# MGD_SCH1.net
KiCad netlist of a schematic drawn in Altium Designer
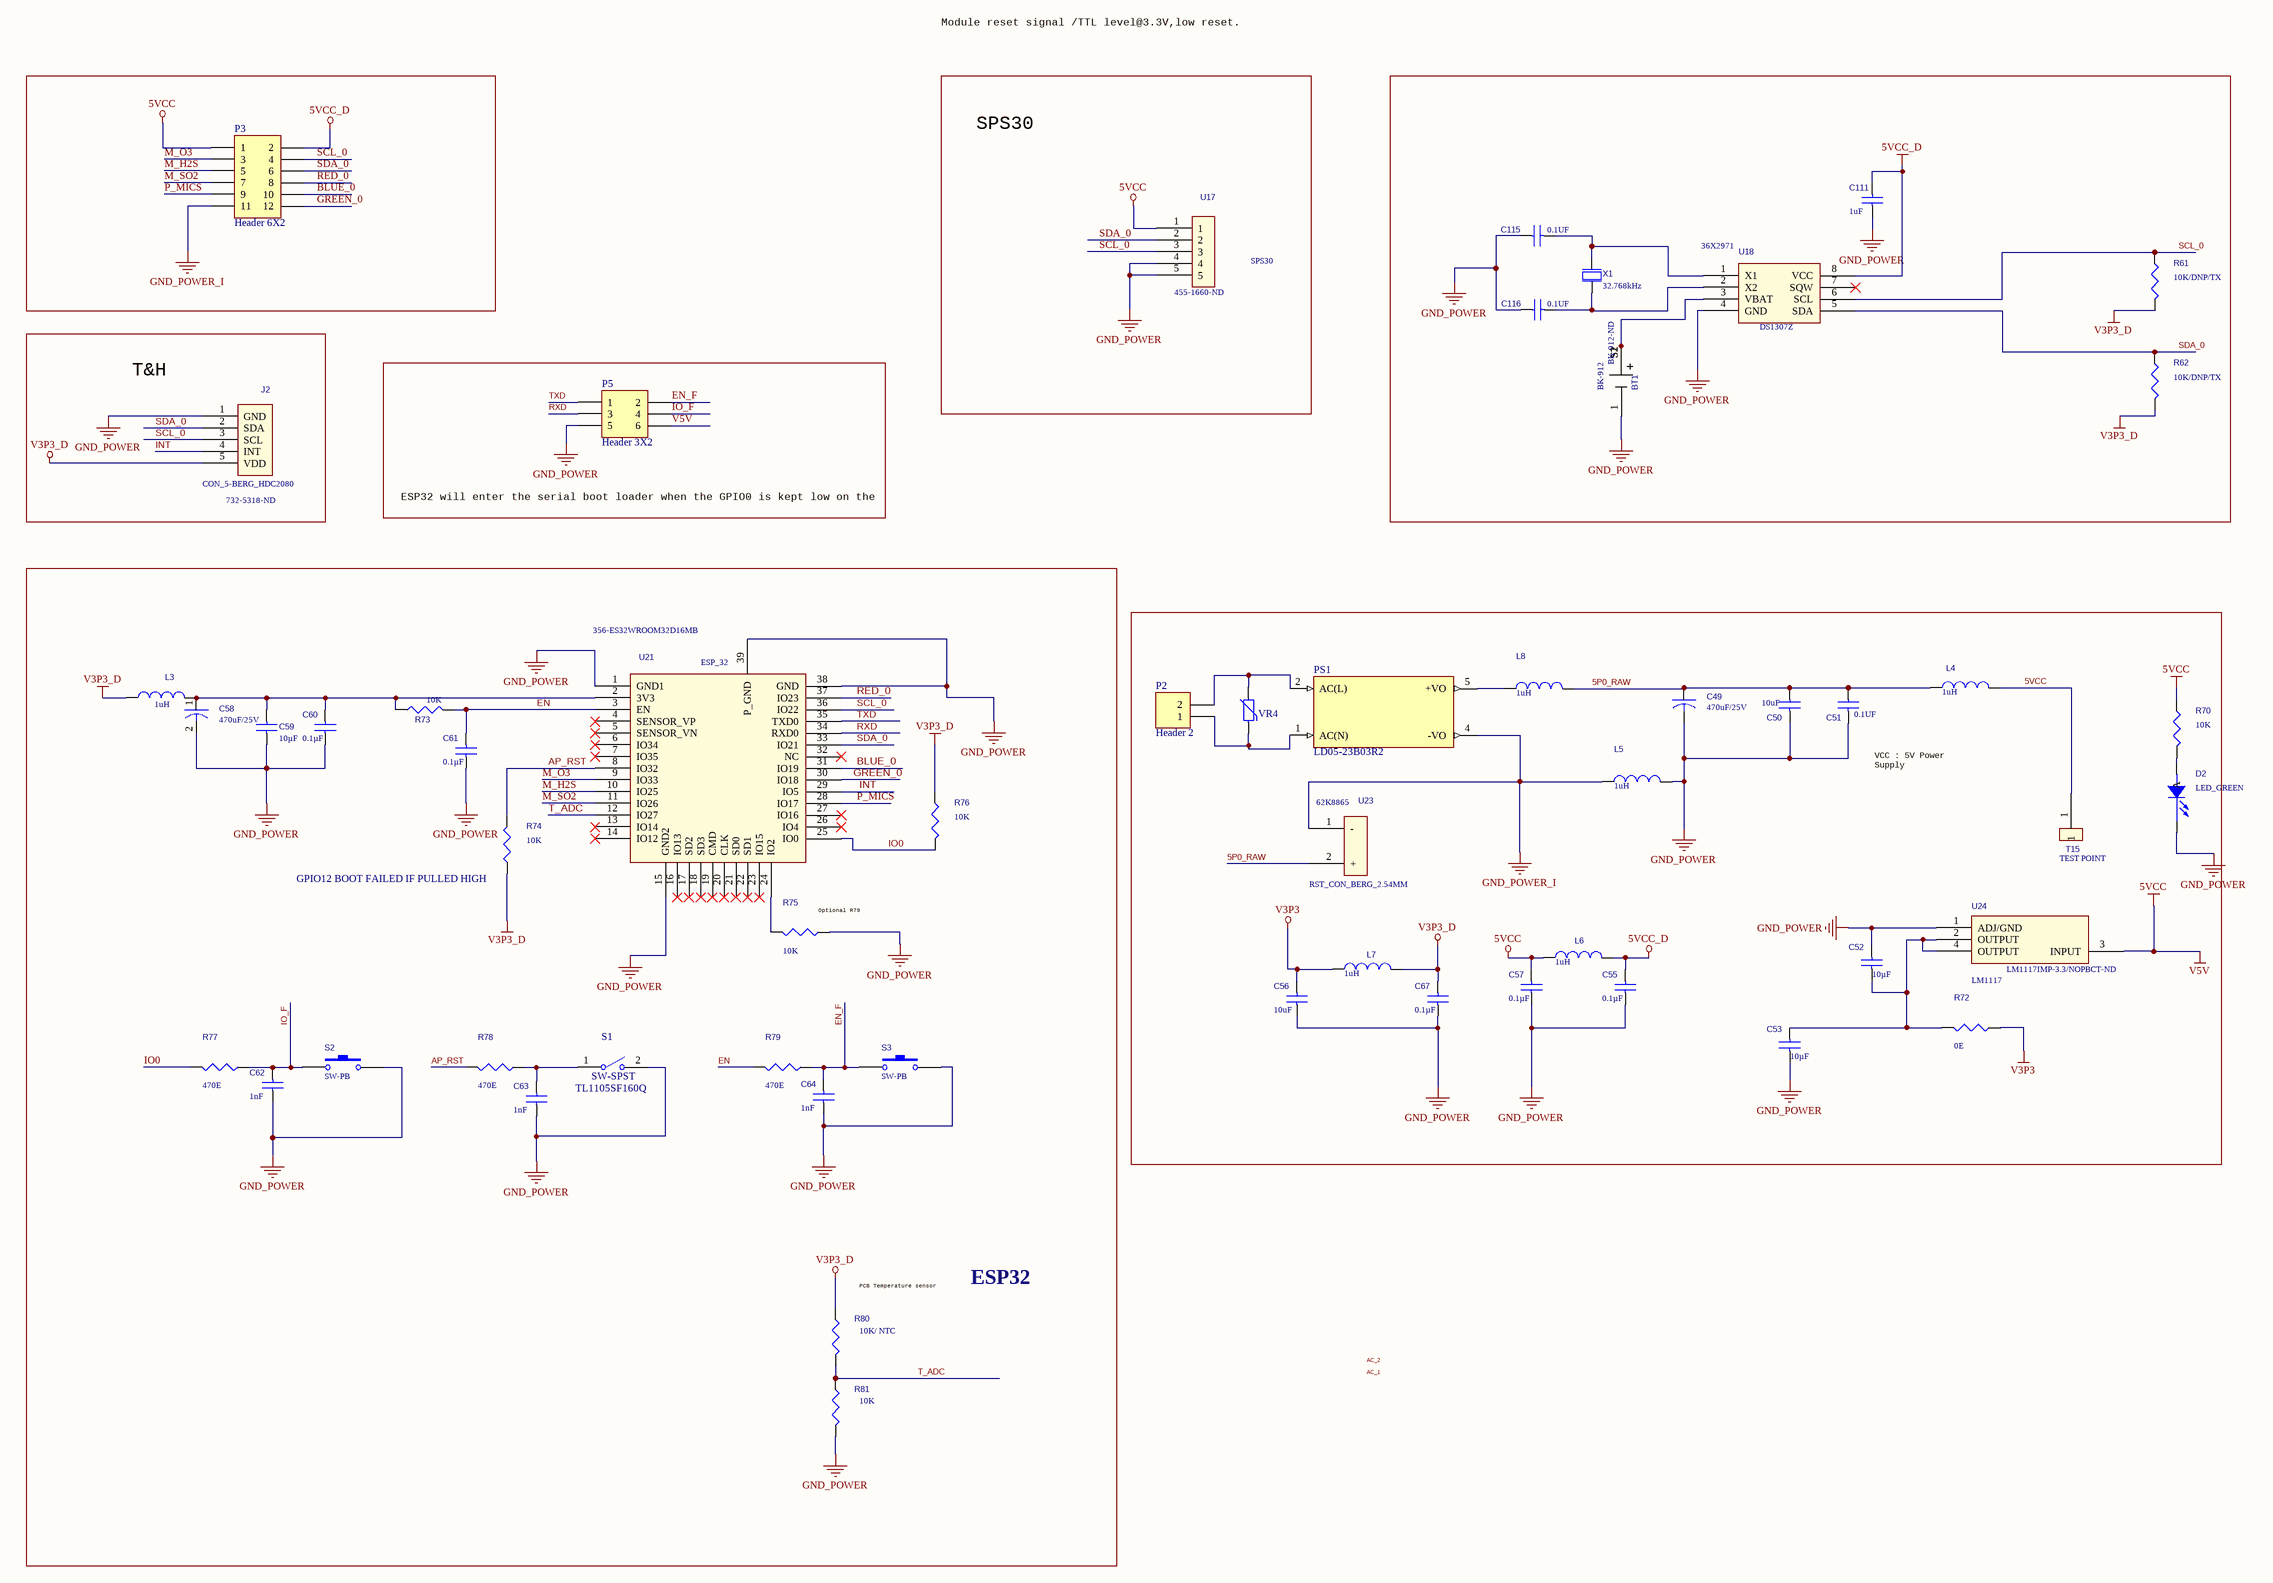
[diagram p0: MGD.SCH1.SchDoc]

(export (version "E")
  (design (tool "Eeschema 10.0.6"))
  (components
    (comp (ref "BT1")
      (value "BK-912")
      (footprint "BT1")
      (description "BATTERY RETAINER COIN 20MM SMD")
      (fields (field (name "MF") "MPD") (field (name "SUPPLIER PART NUMBER 1") "BK-912-ND"))
      (libsource (lib "BK-912") (part "BK-912"))
    )
    (comp (ref "C49")
      (value "470uF/25V")
      (footprint "C16, C49, C58")
      (description "CAP ALUM 470UF 20% 50V RADIAL")
      (fields (field (name "PART NUMBER") "871-B41896E6477M000"))
      (libsource (lib "") (part "CAP_1"))
    )
    (comp (ref "C50")
      (value "10uF")
      (footprint "C0603")
      (description "CAP CER 22UF 10V X5R 0603")
      (fields (field (name "PART NUMBER") "GRM188R61A226ME15D"))
      (libsource (lib "*") (part "CAP NP"))
    )
    (comp (ref "C51")
      (value "0.1UF")
      (footprint "C0603")
      (description "CAP CER 22UF 10V X5R 0603")
      (fields (field (name "PART NUMBER") "GRM188R61A226ME15D"))
      (libsource (lib "*") (part "CAP NP"))
    )
    (comp (ref "C52")
      (value "10µF")
      (footprint "C0603")
      (description "CAP CER SMD 10µF/35V")
      (fields
        (field (name "MANUFACTURER") "Taiyo Yuden")
        (field (name "MANUFACTURER PART NUMBER") "GMK316AB7106KL-TR")
      )
      (libsource (lib "Passive Component") (part "CAP_C_10µF/35V"))
    )
    (comp (ref "C53")
      (value "10µF")
      (footprint "C0603")
      (description "CAP CER SMD 10µF/35V")
      (fields
        (field (name "MANUFACTURER") "Taiyo Yuden")
        (field (name "MANUFACTURER PART NUMBER") "GMK316AB7106KL-TR")
      )
      (libsource (lib "Passive Component") (part "CAP_C_10µF/35V"))
    )
    (comp (ref "C55")
      (value "0.1µF")
      (footprint "C0603")
      (description "CAP CER SMD 0.1µF/16V")
      (fields
        (field (name "MANUFACTURER") "Murata Electronics North America")
        (field (name "MANUFACTURER PART NUMBER") "GRM155R61H104KE19D")
      )
      (libsource (lib "Passive Component") (part "CAP_C_0.1µF/16V"))
    )
    (comp (ref "C56")
      (value "10uF")
      (footprint "C0603")
      (description "CAP CER SMD 0.1µF/16V")
      (fields
        (field (name "MANUFACTURER") "Murata Electronics North America")
        (field (name "MANUFACTURER PART NUMBER") "GRM155R61H104KE19D")
      )
      (libsource (lib "Passive Component") (part "CAP_C_0.1µF/16V"))
    )
    (comp (ref "C57")
      (value "0.1µF")
      (footprint "C0603")
      (description "CAP CER SMD 0.1µF/16V")
      (fields
        (field (name "MANUFACTURER") "Murata Electronics North America")
        (field (name "MANUFACTURER PART NUMBER") "GRM155R61H104KE19D")
      )
      (libsource (lib "Passive Component") (part "CAP_C_0.1µF/16V"))
    )
    (comp (ref "C58")
      (value "470uF/25V")
      (footprint "C16, C49, C58")
      (description "CAP ALUM 470UF 20% 50V RADIAL")
      (fields (field (name "PART NUMBER") "871-B41896E6477M000"))
      (libsource (lib "*") (part "CAP"))
    )
    (comp (ref "C59")
      (value "10µF")
      (footprint "C0603")
      (description "CAP CER SMD 10µF/10V")
      (fields
        (field (name "MANUFACTURER") "Yageo")
        (field (name "MANUFACTURER PART NUMBER") "CC0805ZKY5V6BB106")
      )
      (libsource (lib "Passive Component") (part "CAP_C_10µF/10V"))
    )
    (comp (ref "C60")
      (value "0.1µF")
      (footprint "C0603")
      (description "CAP CER SMD 0.1µF/16V")
      (fields
        (field (name "MANUFACTURER") "Murata Electronics North America")
        (field (name "MANUFACTURER PART NUMBER") "CC0603KRX7R7BB104")
      )
      (libsource (lib "Passive Component") (part "CAP_C_0.1µF/16V"))
    )
    (comp (ref "C61")
      (value "0.1µF")
      (footprint "C0603")
      (description "CAP CER SMD 0.1µF/16V")
      (fields
        (field (name "MANUFACTURER") "Murata Electronics North America")
        (field (name "MANUFACTURER PART NUMBER") "GRM155R61H104KE19D")
      )
      (libsource (lib "Passive Component") (part "CAP_C_0.1µF/16V"))
    )
    (comp (ref "C62")
      (value "1nF")
      (footprint "C0603")
      (description "CAP CER SMD 0.1µF/16V")
      (fields
        (field (name "MANUFACTURER") "Murata Electronics North America")
        (field (name "MANUFACTURER PART NUMBER") "GRM155R61H104KE19D")
      )
      (libsource (lib "Passive Component") (part "CAP_C_0.1µF/16V"))
    )
    (comp (ref "C63")
      (value "1nF")
      (footprint "C0603")
      (description "CAP CER SMD 0.1µF/16V")
      (fields
        (field (name "MANUFACTURER") "Murata Electronics North America")
        (field (name "MANUFACTURER PART NUMBER") "GRM155R61H104KE19D")
      )
      (libsource (lib "Passive Component") (part "CAP_C_0.1µF/16V"))
    )
    (comp (ref "C64")
      (value "1nF")
      (footprint "C0603")
      (description "CAP CER SMD 0.1µF/16V")
      (fields
        (field (name "MANUFACTURER") "Murata Electronics North America")
        (field (name "MANUFACTURER PART NUMBER") "GRM155R61H104KE19D")
      )
      (libsource (lib "Passive Component") (part "CAP_C_0.1µF/16V"))
    )
    (comp (ref "C67")
      (value "0.1µF")
      (footprint "C0603")
      (description "CAP CER SMD 0.1µF/16V")
      (fields
        (field (name "MANUFACTURER") "Murata Electronics North America")
        (field (name "MANUFACTURER PART NUMBER") "GRM155R61H104KE19D")
      )
      (libsource (lib "Passive Component") (part "CAP_C_0.1µF/16V"))
    )
    (comp (ref "C111")
      (value "1uF")
      (footprint "C0603")
      (description "CAP CER SMD 0.1µF/16V")
      (fields
        (field (name "MANUFACTURER") "Murata Electronics North America")
        (field (name "MANUFACTURER PART NUMBER") "GRM155R61H104KE19D")
      )
      (libsource (lib "Passive Component") (part "CAP_C_0.1µF/16V"))
    )
    (comp (ref "C115")
      (value "0.1UF")
      (footprint "C0603")
      (description "CAP CER 22UF 10V X5R 0603")
      (fields (field (name "PART NUMBER") "GRM188R61A226ME15D"))
      (libsource (lib "*") (part "CAP NP"))
    )
    (comp (ref "C116")
      (value "0.1UF")
      (footprint "C0603")
      (description "CAP CER 22UF 10V X5R 0603")
      (fields (field (name "PART NUMBER") "GRM188R61A226ME15D"))
      (libsource (lib "*") (part "CAP NP"))
    )
    (comp (ref "D2")
      (value "LED_GREEN")
      (footprint "D2              L0603")
      (description "LED GREEN CLEAR THIN 0603 SMD")
      (fields
        (field (name "DISTRIBUTOR PART NUMBER") "160-1443-1-ND")
        (field (name "MANUFACTURER PART NUMBER") "160-1443-2-ND")
      )
      (libsource (lib "*") (part "LED"))
    )
    (comp (ref "J2")
      (value "CON_5-BERG_HDC2080")
      (footprint "J2")
      (description "CONN HEADER VERT 5POS 2.54MM")
      (fields
        (field (name "PART NUMBER") "61300511121")
        (field (name "SUPPLIER PART NUMBER 1") "732-5318-ND")
      )
      (libsource (lib "*") (part "5_PIN_CON_0"))
    )
    (comp (ref "L3")
      (value "1uH")
      (footprint "L3, L4, L5, L6, L7")
      (description "FERRITE BEAD 120 OHM 0603 1LN")
      (fields (field (name "PART NUMBER") "490-3996-1-ND"))
      (libsource (lib "*") (part "INDUCTOR"))
    )
    (comp (ref "L4")
      (value "1uH")
      (footprint "L3, L4, L5, L6, L7")
      (description "FERRITE BEAD 120 OHM 0603 1LN")
      (fields (field (name "PART NUMBER") "490-3996-1-ND"))
      (libsource (lib "*") (part "INDUCTOR"))
    )
    (comp (ref "L5")
      (value "1uH")
      (footprint "L3, L4, L5, L6, L7")
      (description "FERRITE BEAD 120 OHM 0603 1LN")
      (fields (field (name "PART NUMBER") "490-3996-1-ND"))
      (libsource (lib "*") (part "INDUCTOR"))
    )
    (comp (ref "L6")
      (value "1uH")
      (footprint "L3, L4, L5, L6, L7")
      (description "FERRITE BEAD 120 OHM 0603 1LN")
      (fields (field (name "PART NUMBER") "490-3996-1-ND"))
      (libsource (lib "*") (part "INDUCTOR"))
    )
    (comp (ref "L7")
      (value "1uH")
      (footprint "L3, L4, L5, L6, L7")
      (description "FERRITE BEAD 120 OHM 0603 1LN")
      (fields (field (name "PART NUMBER") "490-3996-1-ND"))
      (libsource (lib "*") (part "INDUCTOR"))
    )
    (comp (ref "L8")
      (value "1uH")
      (footprint "C0603")
      (description "FERRITE BEAD 120 OHM 0603 1LN")
      (fields (field (name "PART NUMBER") "490-3996-1-ND"))
      (libsource (lib "*") (part "INDUCTOR"))
    )
    (comp (ref "P2")
      (value "Header 2")
      (footprint "TE 282834-2")
      (description "Header, 2-Pin")
      (fields (field (name "PUBLISHER") "Altium Limited"))
      (libsource (lib "Miscellaneous Connectors") (part "Header 2"))
    )
    (comp (ref "P3")
      (value "Header 6X2")
      (footprint "P1,P3_Updated")
      (description "Header, 6-Pin, Dual row")
      (fields (field (name "PUBLISHER") "Altium Limited"))
      (libsource (lib "Miscellaneous Connectors") (part "Header 6X2"))
    )
    (comp (ref "P5")
      (value "Header 3X2")
      (footprint "P5 - new")
      (description "Header, 3-Pin, Dual row")
      (fields (field (name "PUBLISHER") "Altium Limited"))
      (libsource (lib "Miscellaneous Connectors") (part "Header 3X2"))
    )
    (comp (ref "PS1")
      (value "LD05-23B03R2")
      (footprint "CONV_LD05-23B03R2")
      (description "Enclosed AC DC Converters 1 Uitgang 3.3V 1.515A 85 ~ 305 VAC, 100 ~ 430 VDC Input")
      (fields (field (name "MF") "MORNSUN"))
      (libsource (lib "LD05-23B03R2") (part "LD05-23B03R2"))
    )
    (comp (ref "R61")
      (value "10K/DNP/TX")
      (footprint "R0603")
      (description "RES SMD 4.7K OHM 1% 1/16W 0603")
      (fields (field (name "PART NUMBER") "311-10KGRTR-ND"))
      (libsource (lib "*") (part "R"))
    )
    (comp (ref "R62")
      (value "10K/DNP/TX")
      (footprint "R0603")
      (description "RES SMD 4.7K OHM 1% 1/16W 0603")
      (fields (field (name "PART NUMBER") "311-10KGRTR-ND"))
      (libsource (lib "*") (part "R"))
    )
    (comp (ref "R70")
      (value "10K")
      (footprint "R0603")
      (description "RES SMD 1K OHM 5% 1/10W 0603")
      (fields (field (name "PART NUMBER") "311-1.0KGRTR-ND"))
      (libsource (lib "*") (part "R"))
    )
    (comp (ref "R72")
      (value "0E")
      (footprint "R0603")
      (description "RES SMD 470 OHM 1% 1/10W 0603")
      (fields (field (name "PART NUMBER") "311-470HRCT-ND"))
      (libsource (lib "*") (part "R"))
    )
    (comp (ref "R73")
      (value "10K")
      (footprint "R0603")
      (description "RES SMD 4.7K OHM 1% 1/16W 0603")
      (fields (field (name "PART NUMBER") "311-10KGRTR-ND"))
      (libsource (lib "*") (part "R"))
    )
    (comp (ref "R74")
      (value "10K")
      (footprint "R0603")
      (description "RES SMD 4.7K OHM 1% 1/16W 0603")
      (fields (field (name "PART NUMBER") "311-10KGRTR-ND"))
      (libsource (lib "*") (part "R"))
    )
    (comp (ref "R75")
      (value "10K")
      (footprint "R0603")
      (description "RES SMD 4.7K OHM 1% 1/16W 0603")
      (fields (field (name "PART NUMBER") "311-10KGRTR-ND"))
      (libsource (lib "*") (part "R"))
    )
    (comp (ref "R76")
      (value "10K")
      (footprint "R0603")
      (description "RES SMD 4.7K OHM 1% 1/16W 0603")
      (fields (field (name "PART NUMBER") "311-10KGRTR-ND"))
      (libsource (lib "*") (part "R"))
    )
    (comp (ref "R77")
      (value "470E")
      (footprint "R0603")
      (description "RES SMD 470 OHM 1% 1/10W 0603")
      (fields (field (name "PART NUMBER") "311-470HRCT-ND"))
      (libsource (lib "*") (part "R"))
    )
    (comp (ref "R78")
      (value "470E")
      (footprint "R0603")
      (description "RES SMD 470 OHM 1% 1/10W 0603")
      (fields (field (name "PART NUMBER") "311-470HRCT-ND"))
      (libsource (lib "*") (part "R"))
    )
    (comp (ref "R79")
      (value "470E")
      (footprint "R0603")
      (description "RES SMD 470 OHM 1% 1/10W 0603")
      (fields (field (name "PART NUMBER") "311-470HRCT-ND"))
      (libsource (lib "*") (part "R"))
    )
    (comp (ref "R80")
      (value "10K/ NTC")
      (footprint "R0603")
      (description "THERMISTOR NTC 10KOHM 3380K 0603")
      (fields (field (name "PART NUMBER") "490-16279-2-ND"))
      (libsource (lib "*") (part "R"))
    )
    (comp (ref "R81")
      (value "10K")
      (footprint "R0603")
      (description "RES SMD 4.7K OHM 1% 1/16W 0603")
      (fields (field (name "PART NUMBER") "311-10KGRTR-ND"))
      (libsource (lib "*") (part "R"))
    )
    (comp (ref "S1")
      (value "SW-SPST")
      (footprint "S1")
      (description "SWITCH TACTILE SPST-NO 0.05A 12V")
      (fields (field (name "PART NUMBER") "TL1105SF160Q") (field (name "PUBLISHER") "Altium Limited"))
      (libsource (lib "Miscellaneous Devices") (part "SW-SPST"))
    )
    (comp (ref "S2")
      (value "SW-PB")
      (footprint "S2, S3")
      (description "Switch")
      (fields (field (name "PUBLISHER") "Altium Limited"))
      (libsource (lib "Miscellaneous Devices") (part "SW-PB"))
    )
    (comp (ref "S3")
      (value "SW-PB")
      (footprint "S2, S3")
      (description "Switch")
      (fields (field (name "PUBLISHER") "Altium Limited"))
      (libsource (lib "Miscellaneous Devices") (part "SW-PB"))
    )
    (comp (ref "T15") (value "TEST POINT") (footprint "TP") (libsource (lib "*") (part "Test_P")))
    (comp (ref "U17")
      (value "SPS30")
      (footprint "U17")
      (fields
        (field (name "PART NUMBER") "490107670412")
        (field (name "SUPPLIER PART NUMBER 1") "455-1660-ND")
      )
      (libsource (lib "*") (part "PROG_ESP32_0"))
    )
    (comp (ref "U18")
      (value "DS1307Z")
      (footprint "U18 new")
      (description "IC RTC CLK/CALENDAR I2C 8-SOIC")
      (fields (field (name "SUPPLIER PART NUMBER 1") "36X2971"))
      (libsource (lib "*") (part "MP1584_SOIC_0"))
    )
    (comp (ref "U21")
      (value "ESP_32")
      (footprint "U20             ESP 32")
      (description "WIFI MODULE 128MBITS SPI FLASH")
      (fields
        (field (name "PART NUMBER") "356-ES32WROOM32D16MB")
        (field (name "SUPPLIER PART NUMBER 1") "356-ES32WROOM32D16MB")
      )
      (libsource (lib "*") (part "ESP32_SMD_1"))
    )
    (comp (ref "U23")
      (value "RST_CON_BERG_2.54MM")
      (footprint "U23")
      (description "CONN HEADER VERT 2POS 2.54MM")
      (fields (field (name "PART NUMBER") "609-4434-ND") (field (name "SUPPLIER PART NUMBER 1") "62K8865"))
      (libsource (lib "*") (part "CON_AC_1"))
    )
    (comp (ref "U24")
      (value "LM1117")
      (footprint "U1, U24              SOT-223")
      (description "3.3V LDO")
      (fields
        (field (name "MANUFACTURER") "Texas Instruments")
        (field (name "SUPPLIER PART NUMBER 1") "LM1117IMP-3.3/NOPBCT-ND")
      )
      (libsource (lib "PMIC") (part "TLV70033DDCT"))
    )
    (comp (ref "VR4")
      (value "~")
      (footprint "Mov")
      (description "SMT Resistor")
      (libsource (lib "Passive Component") (part "Metal Oxide Variaster"))
    )
    (comp (ref "X1")
      (value "32.768kHz")
      (footprint "XTAL")
      (description "XTAL SMD 3215, 32.768kHz, Cl=9pF, Total Tol: ±50ppm")
      (fields (field (name "PART NUMBER") "XC1911TR-ND") (field (name "PUBLISHER") "Nordic Semiconductor"))
      (libsource (lib "Micro_Controller") (part "XTAL_2-pin"))
    )
  )
  (nets
    (net (code "1") (name "/5P0_RAW") (class "Default")
      (node (ref "C49") (pin "1") (pinfunction "1_1") (pintype "passive"))
      (node (ref "C50") (pin "1") (pinfunction "1_1") (pintype "passive"))
      (node (ref "C51") (pin "1") (pinfunction "1_1") (pintype "passive"))
      (node (ref "L4") (pin "1") (pinfunction "1_1") (pintype "passive"))
      (node (ref "L8") (pin "2") (pinfunction "2_2") (pintype "passive"))
      (node (ref "U23") (pin "2") (pinfunction "+_2") (pintype "passive"))
    )
    (net (code "4") (name "/AP_RST") (class "Default")
      (node (ref "R74") (pin "2") (pinfunction "2_2") (pintype "passive"))
      (node (ref "R78") (pin "2") (pinfunction "2_2") (pintype "passive"))
      (node (ref "U21") (pin "8") (pinfunction "IO32_8") (pintype "passive"))
    )
    (net (code "5") (name "/BLUE_0") (class "Default")
      (node (ref "P3") (pin "10") (pinfunction "10_10") (pintype "passive"))
      (node (ref "U21") (pin "31") (pinfunction "IO19_31") (pintype "passive"))
    )
    (net (code "6") (name "/EN") (class "Default")
      (node (ref "C61") (pin "2") (pinfunction "2_2") (pintype "passive"))
      (node (ref "R73") (pin "2") (pinfunction "2_2") (pintype "passive"))
      (node (ref "R79") (pin "2") (pinfunction "2_2") (pintype "passive"))
      (node (ref "U21") (pin "3") (pinfunction "EN_3") (pintype "passive"))
    )
    (net (code "7") (name "/EN_F") (class "Default")
      (node (ref "C64") (pin "2") (pinfunction "2_2") (pintype "passive"))
      (node (ref "P5") (pin "2") (pinfunction "2_2") (pintype "passive"))
      (node (ref "R79") (pin "1") (pinfunction "1_1") (pintype "passive"))
      (node (ref "S3") (pin "1") (pinfunction "1_1") (pintype "passive"))
    )
    (net (code "8") (name "/GREEN_0") (class "Default")
      (node (ref "P3") (pin "12") (pinfunction "12_12") (pintype "passive"))
      (node (ref "U21") (pin "30") (pinfunction "IO18_30") (pintype "passive"))
    )
    (net (code "9") (name "/INT") (class "Default")
      (node (ref "J2") (pin "4") (pinfunction "INT_4") (pintype "passive"))
      (node (ref "U21") (pin "29") (pinfunction "IO5_29") (pintype "passive"))
    )
    (net (code "10") (name "/IO0") (class "Default")
      (node (ref "R76") (pin "2") (pinfunction "2_2") (pintype "passive"))
      (node (ref "R77") (pin "2") (pinfunction "2_2") (pintype "passive"))
      (node (ref "U21") (pin "25") (pinfunction "IO0_25") (pintype "passive"))
    )
    (net (code "11") (name "/IO_F") (class "Default")
      (node (ref "C62") (pin "2") (pinfunction "2_2") (pintype "passive"))
      (node (ref "P5") (pin "4") (pinfunction "4_4") (pintype "passive"))
      (node (ref "R77") (pin "1") (pinfunction "1_1") (pintype "passive"))
      (node (ref "S2") (pin "1") (pinfunction "1_1") (pintype "passive"))
    )
    (net (code "12") (name "/M_H2S") (class "Default")
      (node (ref "P3") (pin "5") (pinfunction "5_5") (pintype "passive"))
      (node (ref "U21") (pin "10") (pinfunction "IO25_10") (pintype "passive"))
    )
    (net (code "13") (name "/M_O3") (class "Default")
      (node (ref "P3") (pin "3") (pinfunction "3_3") (pintype "passive"))
      (node (ref "U21") (pin "9") (pinfunction "IO33_9") (pintype "passive"))
    )
    (net (code "14") (name "/M_SO2") (class "Default")
      (node (ref "P3") (pin "7") (pinfunction "7_7") (pintype "passive"))
      (node (ref "U21") (pin "11") (pinfunction "IO26_11") (pintype "passive"))
    )
    (net (code "15") (name "/P_MICS") (class "Default")
      (node (ref "P3") (pin "9") (pinfunction "9_9") (pintype "passive"))
      (node (ref "U21") (pin "28") (pinfunction "IO17_28") (pintype "passive"))
    )
    (net (code "16") (name "/RED_0") (class "Default")
      (node (ref "P3") (pin "8") (pinfunction "8_8") (pintype "passive"))
      (node (ref "U21") (pin "37") (pinfunction "IO23_37") (pintype "passive"))
    )
    (net (code "17") (name "/RXD") (class "Default")
      (node (ref "P5") (pin "3") (pinfunction "3_3") (pintype "passive"))
      (node (ref "U21") (pin "34") (pinfunction "RXD0_34") (pintype "passive"))
    )
    (net (code "18") (name "/SCL_0") (class "Default")
      (node (ref "J2") (pin "3") (pinfunction "SCL_3") (pintype "passive"))
      (node (ref "P3") (pin "4") (pinfunction "4_4") (pintype "passive"))
      (node (ref "R61") (pin "1") (pinfunction "1_1") (pintype "passive"))
      (node (ref "U17") (pin "3") (pinfunction "3_3") (pintype "passive"))
      (node (ref "U18") (pin "6") (pinfunction "SCL_6") (pintype "passive"))
      (node (ref "U21") (pin "36") (pinfunction "IO22_36") (pintype "passive"))
    )
    (net (code "19") (name "/SDA_0") (class "Default")
      (node (ref "J2") (pin "2") (pinfunction "SDA_2") (pintype "passive"))
      (node (ref "P3") (pin "6") (pinfunction "6_6") (pintype "passive"))
      (node (ref "R62") (pin "1") (pinfunction "1_1") (pintype "passive"))
      (node (ref "U17") (pin "2") (pinfunction "2_2") (pintype "passive"))
      (node (ref "U18") (pin "5") (pinfunction "SDA_5") (pintype "passive"))
      (node (ref "U21") (pin "33") (pinfunction "IO21_33") (pintype "passive"))
    )
    (net (code "20") (name "/TXD") (class "Default")
      (node (ref "P5") (pin "1") (pinfunction "1_1") (pintype "passive"))
      (node (ref "U21") (pin "35") (pinfunction "TXD0_35") (pintype "passive"))
    )
    (net (code "21") (name "/T_ADC") (class "Default")
      (node (ref "R80") (pin "2") (pinfunction "2_2") (pintype "passive"))
      (node (ref "R81") (pin "1") (pinfunction "1_1") (pintype "passive"))
      (node (ref "U21") (pin "12") (pinfunction "IO27_12") (pintype "passive"))
    )
    (net (code "22") (name "5VCC") (class "Default")
      (node (ref "C57") (pin "2") (pinfunction "2_2") (pintype "passive"))
      (node (ref "L4") (pin "2") (pinfunction "2_2") (pintype "passive"))
      (node (ref "L6") (pin "1") (pinfunction "1_1") (pintype "passive"))
      (node (ref "P3") (pin "1") (pinfunction "1_1") (pintype "passive"))
      (node (ref "P5") (pin "6") (pinfunction "6_6") (pintype "passive"))
      (node (ref "R70") (pin "1") (pinfunction "1_1") (pintype "passive"))
      (node (ref "T15") (pin "1") (pinfunction "1_1") (pintype "passive"))
      (node (ref "U17") (pin "1") (pinfunction "1_1") (pintype "passive"))
      (node (ref "U24") (pin "3") (pinfunction "INPUT_3") (pintype "passive"))
    )
    (net (code "23") (name "5VCC_D") (class "Default")
      (node (ref "C111") (pin "2") (pinfunction "2_2") (pintype "passive"))
      (node (ref "C55") (pin "2") (pinfunction "2_2") (pintype "passive"))
      (node (ref "L6") (pin "2") (pinfunction "2_2") (pintype "passive"))
      (node (ref "P3") (pin "2") (pinfunction "2_2") (pintype "passive"))
      (node (ref "U18") (pin "8") (pinfunction "VCC_8") (pintype "power_in"))
    )
    (net (code "24") (name "GND_POWER") (class "Default")
      (node (ref "BT1") (pin "1") (pinfunction "NEG_1") (pintype "passive"))
      (node (ref "C111") (pin "1") (pinfunction "1_1") (pintype "passive"))
      (node (ref "C115") (pin "1") (pinfunction "1_1") (pintype "passive"))
      (node (ref "C116") (pin "1") (pinfunction "1_1") (pintype "passive"))
      (node (ref "C49") (pin "2") (pinfunction "2_2") (pintype "passive"))
      (node (ref "C50") (pin "2") (pinfunction "2_2") (pintype "passive"))
      (node (ref "C51") (pin "2") (pinfunction "2_2") (pintype "passive"))
      (node (ref "C52") (pin "1") (pinfunction "1_1") (pintype "passive"))
      (node (ref "C53") (pin "2") (pinfunction "2_2") (pintype "passive"))
      (node (ref "C55") (pin "1") (pinfunction "1_1") (pintype "passive"))
      (node (ref "C56") (pin "1") (pinfunction "1_1") (pintype "passive"))
      (node (ref "C57") (pin "1") (pinfunction "1_1") (pintype "passive"))
      (node (ref "C58") (pin "2") (pinfunction "2_2") (pintype "passive"))
      (node (ref "C59") (pin "1") (pinfunction "1_1") (pintype "passive"))
      (node (ref "C60") (pin "1") (pinfunction "1_1") (pintype "passive"))
      (node (ref "C61") (pin "1") (pinfunction "1_1") (pintype "passive"))
      (node (ref "C62") (pin "1") (pinfunction "1_1") (pintype "passive"))
      (node (ref "C63") (pin "1") (pinfunction "1_1") (pintype "passive"))
      (node (ref "C64") (pin "1") (pinfunction "1_1") (pintype "passive"))
      (node (ref "C67") (pin "1") (pinfunction "1_1") (pintype "passive"))
      (node (ref "D2") (pin "2") (pinfunction "CATHODE_2") (pintype "passive"))
      (node (ref "J2") (pin "1") (pinfunction "GND_1") (pintype "passive"))
      (node (ref "L5") (pin "2") (pinfunction "2_2") (pintype "passive"))
      (node (ref "P5") (pin "5") (pinfunction "5_5") (pintype "passive"))
      (node (ref "R75") (pin "1") (pinfunction "1_1") (pintype "passive"))
      (node (ref "R81") (pin "2") (pinfunction "2_2") (pintype "passive"))
      (node (ref "S1") (pin "2") (pinfunction "NO_2") (pintype "passive"))
      (node (ref "S2") (pin "2") (pinfunction "2_2") (pintype "passive"))
      (node (ref "S3") (pin "2") (pinfunction "2_2") (pintype "passive"))
      (node (ref "U17") (pin "4") (pinfunction "4_4") (pintype "passive"))
      (node (ref "U17") (pin "5") (pinfunction "5_5") (pintype "passive"))
      (node (ref "U18") (pin "4") (pinfunction "GND_4") (pintype "power_in"))
      (node (ref "U21") (pin "1") (pinfunction "GND1_1") (pintype "passive"))
      (node (ref "U21") (pin "15") (pinfunction "GND2_15") (pintype "passive"))
      (node (ref "U21") (pin "38") (pinfunction "GND_38") (pintype "passive"))
      (node (ref "U21") (pin "39") (pinfunction "P_GND_39") (pintype "passive"))
      (node (ref "U24") (pin "1") (pinfunction "ADJ/GND_1") (pintype "passive"))
    )
    (net (code "25") (name "GND_POWER_I") (class "Default")
      (node (ref "L5") (pin "1") (pinfunction "1_1") (pintype "passive"))
      (node (ref "P3") (pin "11") (pinfunction "11_11") (pintype "passive"))
      (node (ref "PS1") (pin "4") (pinfunction "-VO_4") (pintype "output"))
      (node (ref "U23") (pin "1") (pinfunction "-_1") (pintype "passive"))
    )
    (net (code "26") (name "Net-(C52-Pad2)") (class "Default")
      (node (ref "C52") (pin "2") (pinfunction "2_2") (pintype "passive"))
      (node (ref "C53") (pin "1") (pinfunction "1_1") (pintype "passive"))
      (node (ref "R72") (pin "2") (pinfunction "2_2") (pintype "passive"))
      (node (ref "U24") (pin "2") (pinfunction "OUTPUT_2") (pintype "passive"))
      (node (ref "U24") (pin "4") (pinfunction "OUTPUT_4") (pintype "passive"))
    )
    (net (code "27") (name "Net-(D2-A)") (class "Default")
      (node (ref "D2") (pin "1") (pinfunction "A_1") (pintype "passive"))
      (node (ref "R70") (pin "2") (pinfunction "2_2") (pintype "passive"))
    )
    (net (code "28") (name "Net-(PS1-+VO)") (class "Default")
      (node (ref "L8") (pin "1") (pinfunction "1_1") (pintype "passive"))
      (node (ref "PS1") (pin "5") (pinfunction "+VO_5") (pintype "output"))
    )
    (net (code "29") (name "Net-(PS1-AC(L))") (class "Default")
      (node (ref "P2") (pin "2") (pinfunction "2_2") (pintype "passive"))
      (node (ref "PS1") (pin "2") (pinfunction "AC(L)_2") (pintype "input"))
      (node (ref "VR4") (pin "2") (pinfunction "2_2") (pintype "passive"))
    )
    (net (code "30") (name "Net-(PS1-AC(N))") (class "Default")
      (node (ref "P2") (pin "1") (pinfunction "1_1") (pintype "passive"))
      (node (ref "PS1") (pin "1") (pinfunction "AC(N)_1") (pintype "input"))
      (node (ref "VR4") (pin "1") (pinfunction "1_1") (pintype "passive"))
    )
    (net (code "31") (name "Net-(S1-COMMON)") (class "Default")
      (node (ref "C63") (pin "2") (pinfunction "2_2") (pintype "passive"))
      (node (ref "R78") (pin "1") (pinfunction "1_1") (pintype "passive"))
      (node (ref "S1") (pin "1") (pinfunction "COMMON_1") (pintype "passive"))
    )
    (net (code "32") (name "Net-(U18-VBAT)") (class "Default")
      (node (ref "BT1") (pin "S1") (pinfunction "POS_S1") (pintype "passive"))
      (node (ref "BT1") (pin "S2") (pinfunction "POS_S2") (pintype "passive"))
      (node (ref "U18") (pin "3") (pinfunction "VBAT_3") (pintype "passive"))
    )
    (net (code "33") (name "Net-(U18-X1)") (class "Default")
      (node (ref "C115") (pin "2") (pinfunction "2_2") (pintype "passive"))
      (node (ref "U18") (pin "1") (pinfunction "X1_1") (pintype "passive"))
      (node (ref "X1") (pin "1") (pinfunction "inp_1") (pintype "passive"))
    )
    (net (code "34") (name "Net-(U18-X2)") (class "Default")
      (node (ref "C116") (pin "2") (pinfunction "2_2") (pintype "passive"))
      (node (ref "U18") (pin "2") (pinfunction "X2_2") (pintype "passive"))
      (node (ref "X1") (pin "2") (pinfunction "out_2") (pintype "passive"))
    )
    (net (code "35") (name "Net-(U21-3V3)") (class "Default")
      (node (ref "C58") (pin "1") (pinfunction "1_1") (pintype "passive"))
      (node (ref "C59") (pin "2") (pinfunction "2_2") (pintype "passive"))
      (node (ref "C60") (pin "2") (pinfunction "2_2") (pintype "passive"))
      (node (ref "L3") (pin "2") (pinfunction "2_2") (pintype "passive"))
      (node (ref "R73") (pin "1") (pinfunction "1_1") (pintype "passive"))
      (node (ref "U21") (pin "2") (pinfunction "3V3_2") (pintype "passive"))
    )
    (net (code "36") (name "Net-(U21-IO2)") (class "Default")
      (node (ref "R75") (pin "2") (pinfunction "2_2") (pintype "passive"))
      (node (ref "U21") (pin "24") (pinfunction "IO2_24") (pintype "passive"))
    )
    (net (code "37") (name "V3P3") (class "Default")
      (node (ref "C56") (pin "2") (pinfunction "2_2") (pintype "passive"))
      (node (ref "L7") (pin "1") (pinfunction "1_1") (pintype "passive"))
      (node (ref "R72") (pin "1") (pinfunction "1_1") (pintype "passive"))
    )
    (net (code "38") (name "V3P3_D") (class "Default")
      (node (ref "C67") (pin "2") (pinfunction "2_2") (pintype "passive"))
      (node (ref "J2") (pin "5") (pinfunction "VDD_5") (pintype "passive"))
      (node (ref "L3") (pin "1") (pinfunction "1_1") (pintype "passive"))
      (node (ref "L7") (pin "2") (pinfunction "2_2") (pintype "passive"))
      (node (ref "R61") (pin "2") (pinfunction "2_2") (pintype "passive"))
      (node (ref "R62") (pin "2") (pinfunction "2_2") (pintype "passive"))
      (node (ref "R74") (pin "1") (pinfunction "1_1") (pintype "passive"))
      (node (ref "R76") (pin "1") (pinfunction "1_1") (pintype "passive"))
      (node (ref "R80") (pin "1") (pinfunction "1_1") (pintype "passive"))
    )
    (net (code "39") (name "unconnected-(U18-SQW-Pad7)") (class "Default")
      (node (ref "U18") (pin "7") (pinfunction "SQW_7") (pintype "passive+no_connect"))
    )
    (net (code "40") (name "unconnected-(U21-CLK-Pad20)") (class "Default")
      (node (ref "U21") (pin "20") (pinfunction "CLK_20") (pintype "passive+no_connect"))
    )
    (net (code "41") (name "unconnected-(U21-CMD-Pad19)") (class "Default")
      (node (ref "U21") (pin "19") (pinfunction "CMD_19") (pintype "passive+no_connect"))
    )
    (net (code "42") (name "unconnected-(U21-IO4-Pad26)") (class "Default")
      (node (ref "U21") (pin "26") (pinfunction "IO4_26") (pintype "passive+no_connect"))
    )
    (net (code "43") (name "unconnected-(U21-IO12-Pad14)") (class "Default")
      (node (ref "U21") (pin "14") (pinfunction "IO12_14") (pintype "passive+no_connect"))
    )
    (net (code "44") (name "unconnected-(U21-IO13-Pad16)") (class "Default")
      (node (ref "U21") (pin "16") (pinfunction "IO13_16") (pintype "passive+no_connect"))
    )
    (net (code "45") (name "unconnected-(U21-IO14-Pad13)") (class "Default")
      (node (ref "U21") (pin "13") (pinfunction "IO14_13") (pintype "passive+no_connect"))
    )
    (net (code "46") (name "unconnected-(U21-IO15-Pad23)") (class "Default")
      (node (ref "U21") (pin "23") (pinfunction "IO15_23") (pintype "passive+no_connect"))
    )
    (net (code "47") (name "unconnected-(U21-IO16-Pad27)") (class "Default")
      (node (ref "U21") (pin "27") (pinfunction "IO16_27") (pintype "passive+no_connect"))
    )
    (net (code "48") (name "unconnected-(U21-IO34-Pad6)") (class "Default")
      (node (ref "U21") (pin "6") (pinfunction "IO34_6") (pintype "passive+no_connect"))
    )
    (net (code "49") (name "unconnected-(U21-IO35-Pad7)") (class "Default")
      (node (ref "U21") (pin "7") (pinfunction "IO35_7") (pintype "passive+no_connect"))
    )
    (net (code "50") (name "unconnected-(U21-NC-Pad32)") (class "Default")
      (node (ref "U21") (pin "32") (pinfunction "NC_32") (pintype "passive+no_connect"))
    )
    (net (code "51") (name "unconnected-(U21-SD0-Pad21)") (class "Default")
      (node (ref "U21") (pin "21") (pinfunction "SD0_21") (pintype "passive+no_connect"))
    )
    (net (code "52") (name "unconnected-(U21-SD1-Pad22)") (class "Default")
      (node (ref "U21") (pin "22") (pinfunction "SD1_22") (pintype "passive+no_connect"))
    )
    (net (code "53") (name "unconnected-(U21-SD2-Pad17)") (class "Default")
      (node (ref "U21") (pin "17") (pinfunction "SD2_17") (pintype "passive+no_connect"))
    )
    (net (code "54") (name "unconnected-(U21-SD3-Pad18)") (class "Default")
      (node (ref "U21") (pin "18") (pinfunction "SD3_18") (pintype "passive+no_connect"))
    )
    (net (code "55") (name "unconnected-(U21-SENSOR_VN-Pad5)") (class "Default")
      (node (ref "U21") (pin "5") (pinfunction "SENSOR_VN_5") (pintype "passive+no_connect"))
    )
    (net (code "56") (name "unconnected-(U21-SENSOR_VP-Pad4)") (class "Default")
      (node (ref "U21") (pin "4") (pinfunction "SENSOR_VP_4") (pintype "passive+no_connect"))
    )
  )
)
